# Breakouts3.net
KiCad netlist of a schematic drawn in EAGLE
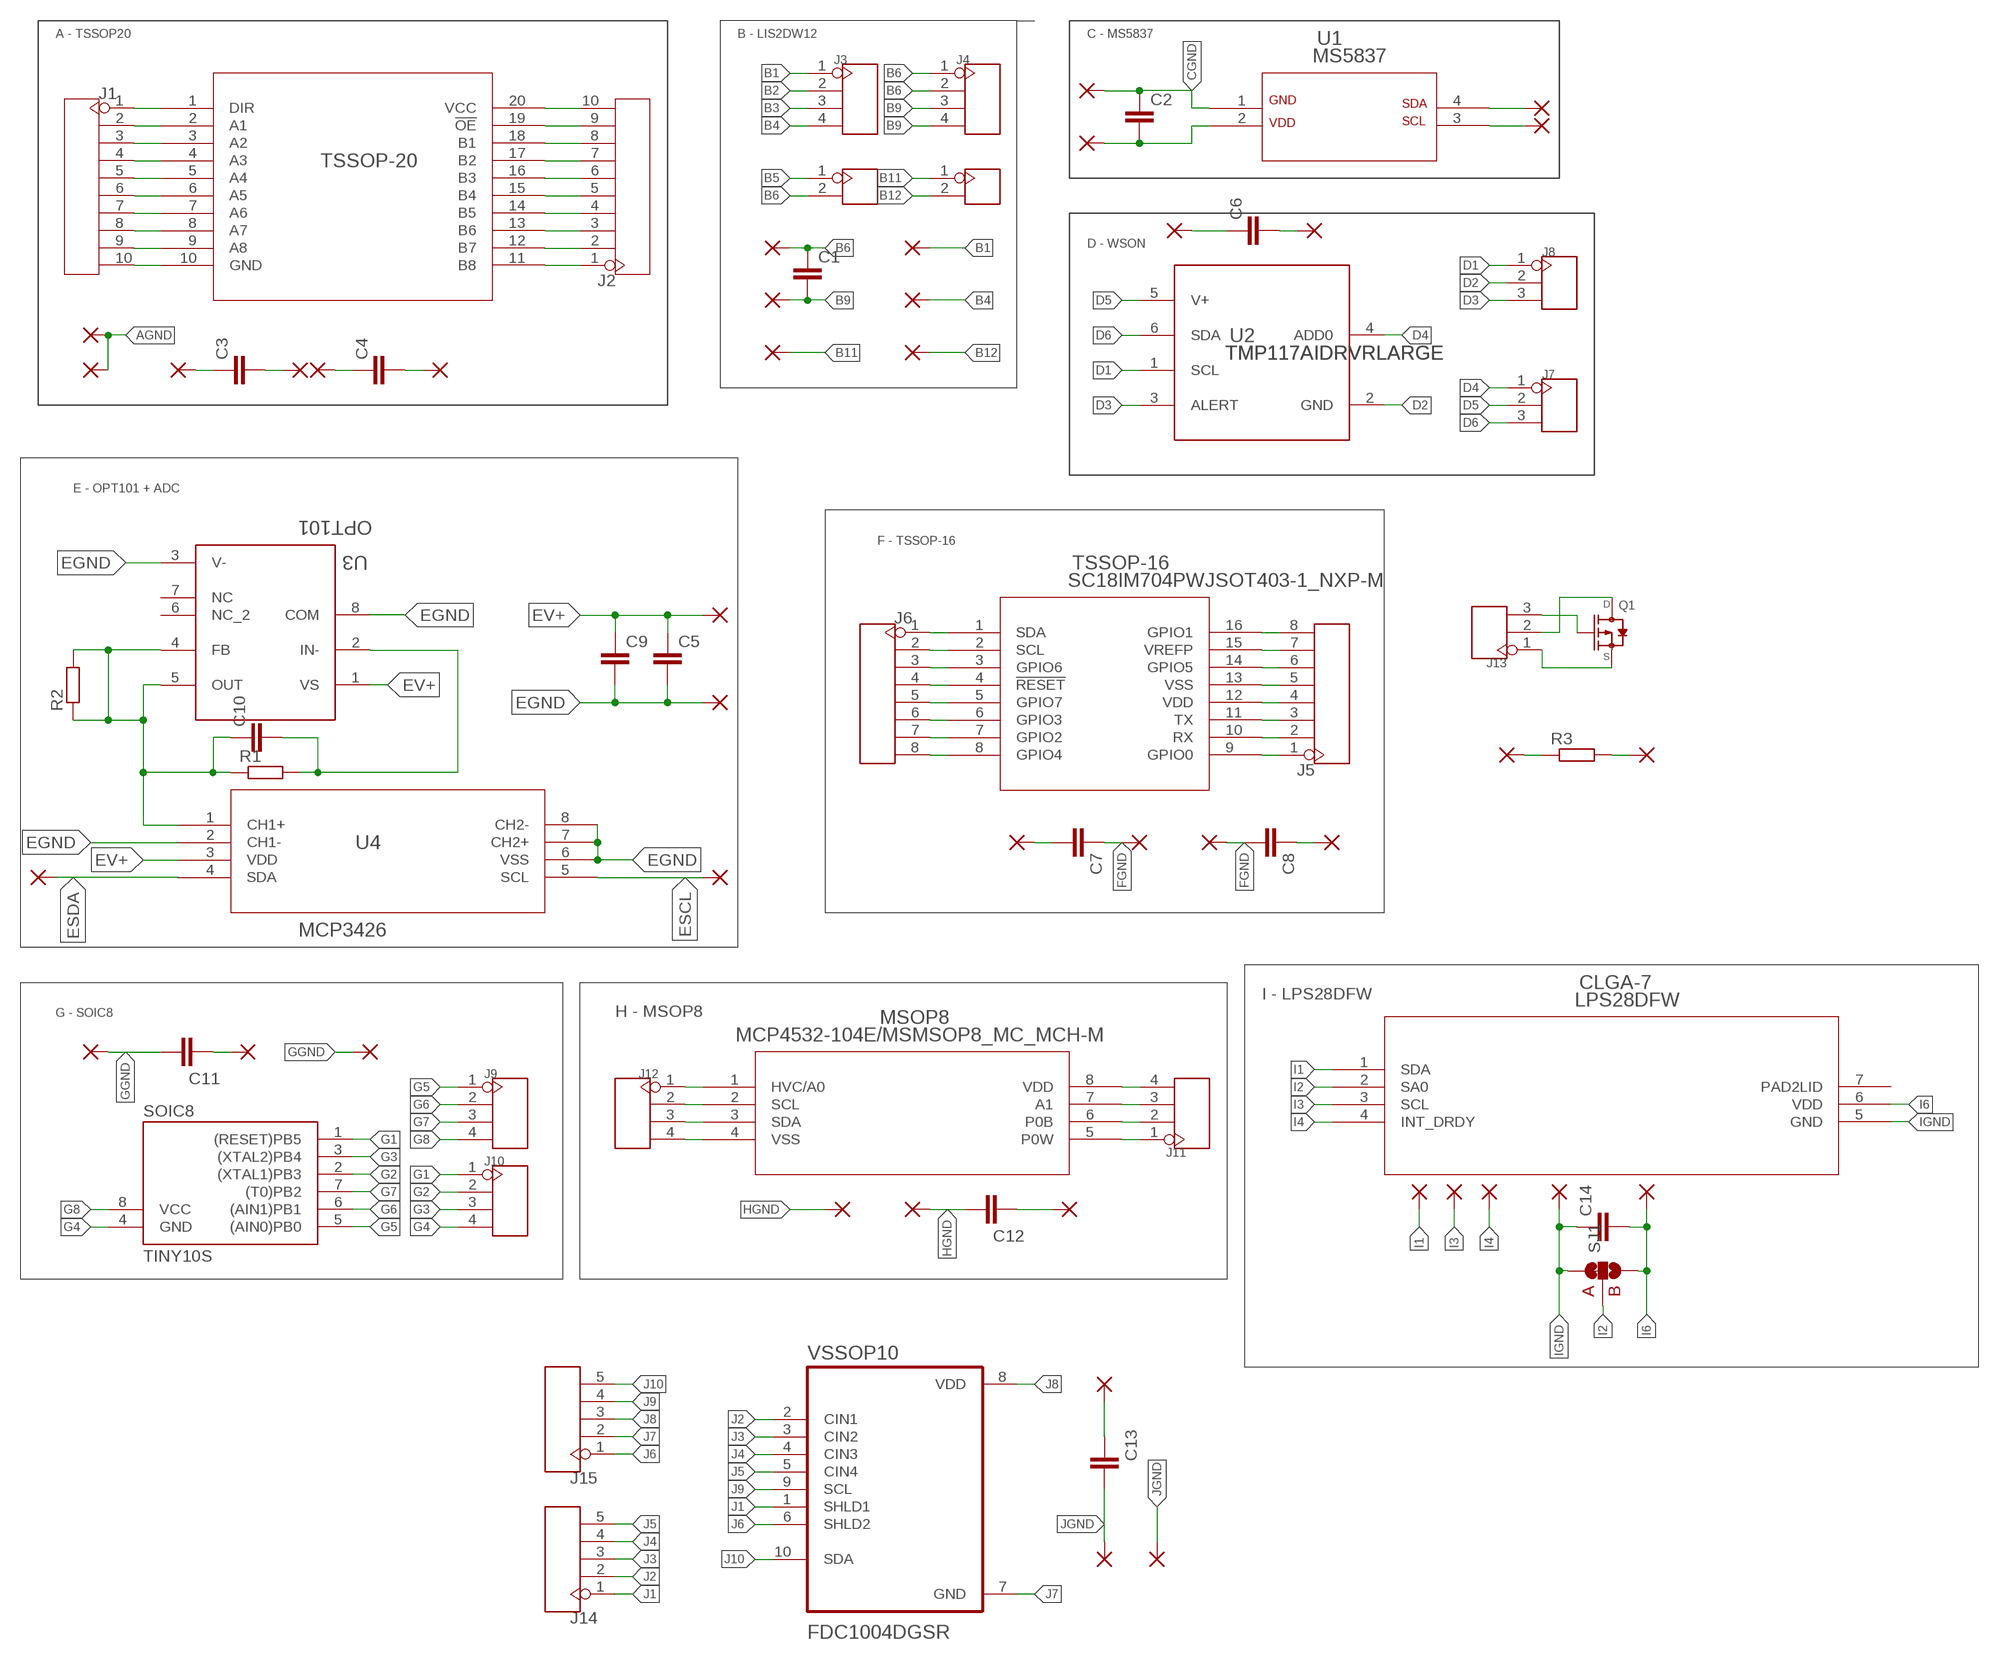
[diagram p0: schematic, sheet 1]

(export (version "E")
  (design (tool "Eeschema 10.0.6"))
  (components
    (comp (ref "C1")
      (value "C-EU1206")
      (footprint "eagle-import:1206")
      (libsource (lib "eagle-import") (part "C-EU1206"))
    )
    (comp (ref "C2")
      (value "C-EU1206")
      (footprint "eagle-import:1206")
      (libsource (lib "eagle-import") (part "C-EU1206"))
    )
    (comp (ref "C3")
      (value "C-EU1206")
      (footprint "eagle-import:1206")
      (libsource (lib "eagle-import") (part "C-EU1206"))
    )
    (comp (ref "C4")
      (value "C-EU1206")
      (footprint "eagle-import:1206")
      (libsource (lib "eagle-import") (part "C-EU1206"))
    )
    (comp (ref "C5")
      (value "C-EU1206")
      (footprint "eagle-import:1206")
      (libsource (lib "eagle-import") (part "C-EU1206"))
    )
    (comp (ref "C6")
      (value "C-EU1206")
      (footprint "eagle-import:1206")
      (libsource (lib "eagle-import") (part "C-EU1206"))
    )
    (comp (ref "C7")
      (value "C-EU1206")
      (footprint "eagle-import:1206")
      (libsource (lib "eagle-import") (part "C-EU1206"))
    )
    (comp (ref "C8")
      (value "C-EU1206")
      (footprint "eagle-import:1206")
      (libsource (lib "eagle-import") (part "C-EU1206"))
    )
    (comp (ref "C9")
      (value "C-EU1206")
      (footprint "eagle-import:1206")
      (libsource (lib "eagle-import") (part "C-EU1206"))
    )
    (comp (ref "C10")
      (value "C-EU1206")
      (footprint "eagle-import:1206")
      (libsource (lib "eagle-import") (part "C-EU1206"))
    )
    (comp (ref "C11")
      (value "C-EU1206")
      (footprint "eagle-import:1206")
      (libsource (lib "eagle-import") (part "C-EU1206"))
    )
    (comp (ref "C12")
      (value "C-EU1206")
      (footprint "eagle-import:1206")
      (libsource (lib "eagle-import") (part "C-EU1206"))
    )
    (comp (ref "C13")
      (value "C-EU1206")
      (footprint "eagle-import:1206")
      (libsource (lib "eagle-import") (part "C-EU1206"))
    )
    (comp (ref "C14")
      (value "C-EU1206")
      (footprint "eagle-import:1206")
      (libsource (lib "eagle-import") (part "C-EU1206"))
    )
    (comp (ref "CLGA-7")
      (value "LPS28DFW")
      (footprint "eagle-import:CCLGA7_LPS28DFW_LARGE")
      (libsource (lib "eagle-import") (part "LPS28DFWTRLARGE"))
    )
    (comp (ref "J1")
      (value "HEADER-10P-2.54")
      (footprint "eagle-import:10P-2.54")
      (libsource (lib "eagle-import") (part "HEADER-10P-2.54"))
    )
    (comp (ref "J2")
      (value "HEADER-10P-2.54")
      (footprint "eagle-import:10P-2.54")
      (libsource (lib "eagle-import") (part "HEADER-10P-2.54"))
    )
    (comp (ref "J3")
      (value "HEADER-4P-SMD-1.27")
      (footprint "eagle-import:4P-1.27-SMD")
      (libsource (lib "eagle-import") (part "SMD Breakouts_HEADER-4P-SMD-1.27"))
    )
    (comp (ref "J4")
      (value "HEADER-4P-SMD-1.27")
      (footprint "eagle-import:4P-1.27-SMD")
      (libsource (lib "eagle-import") (part "SMD Breakouts_HEADER-4P-SMD-1.27"))
    )
    (comp (ref "J5")
      (value "HEADER-8P-2.54")
      (footprint "eagle-import:8P-2.54")
      (libsource (lib "eagle-import") (part "HEADER-8P-2.54"))
    )
    (comp (ref "J6")
      (value "HEADER-8P-2.54")
      (footprint "eagle-import:8P-2.54")
      (libsource (lib "eagle-import") (part "HEADER-8P-2.54"))
    )
    (comp (ref "J7")
      (value "HEADER-3P-2.54")
      (footprint "eagle-import:3P-2.54")
      (libsource (lib "eagle-import") (part "HEADER-3P-2.54"))
    )
    (comp (ref "J8")
      (value "HEADER-3P-2.54")
      (footprint "eagle-import:3P-2.54")
      (libsource (lib "eagle-import") (part "HEADER-3P-2.54"))
    )
    (comp (ref "J9")
      (value "HEADER-4P-60/35MIL")
      (footprint "eagle-import:4P-65_35MIL")
      (libsource (lib "eagle-import") (part "HEADER-4P-60/35MIL"))
    )
    (comp (ref "J10")
      (value "HEADER-4P-60/35MIL")
      (footprint "eagle-import:4P-65_35MIL")
      (libsource (lib "eagle-import") (part "HEADER-4P-60/35MIL"))
    )
    (comp (ref "J11")
      (value "HEADER-4P-60/35MIL")
      (footprint "eagle-import:4P-65_35MIL")
      (libsource (lib "eagle-import") (part "HEADER-4P-60/35MIL"))
    )
    (comp (ref "J12")
      (value "HEADER-4P-60/35MIL")
      (footprint "eagle-import:4P-65_35MIL")
      (libsource (lib "eagle-import") (part "HEADER-4P-60/35MIL"))
    )
    (comp (ref "J13")
      (value "HEADER-3P-2.54")
      (footprint "eagle-import:3P-2.54")
      (libsource (lib "eagle-import") (part "HEADER-3P-2.54"))
    )
    (comp (ref "J14")
      (value "HEADER-5P-2.54")
      (footprint "eagle-import:5P-2.54")
      (libsource (lib "eagle-import") (part "HEADER-5P-2.54"))
    )
    (comp (ref "J15")
      (value "HEADER-5P-2.54")
      (footprint "eagle-import:5P-2.54")
      (libsource (lib "eagle-import") (part "HEADER-5P-2.54"))
    )
    (comp (ref "MSOP8")
      (value "MCP4532-104E/MSMSOP8_MC_MCH-M")
      (footprint "eagle-import:MSOP8_MC_MCH-M")
      (fields
        (field (name "MANUFACTURER_PART_NUMBER") "MCP4532-104E/MS")
        (field (name "COPYRIGHT") "Copyright (C) 2025 Ultra Librarian. All rights reserved.")
      )
      (libsource (lib "eagle-import") (part "MCP4532-104E/MSMSOP8_MC_MCH-M"))
    )
    (comp (ref "PAD1")
      (value "WIREPADSMD1,27-254")
      (footprint "eagle-import:SMD1,27-2,54")
      (libsource (lib "eagle-import") (part "WIREPADSMD1,27-254"))
    )
    (comp (ref "PAD2")
      (value "WIREPADSMD1,27-254")
      (footprint "eagle-import:SMD1,27-2,54")
      (libsource (lib "eagle-import") (part "WIREPADSMD1,27-254"))
    )
    (comp (ref "PAD3")
      (value "WIREPADSMD1,27-254")
      (footprint "eagle-import:SMD1,27-2,54")
      (libsource (lib "eagle-import") (part "WIREPADSMD1,27-254"))
    )
    (comp (ref "PAD4")
      (value "WIREPADSMD1,27-254")
      (footprint "eagle-import:SMD1,27-2,54")
      (libsource (lib "eagle-import") (part "WIREPADSMD1,27-254"))
    )
    (comp (ref "PAD5")
      (value "WIREPADSMD1,27-254")
      (footprint "eagle-import:SMD1,27-2,54")
      (libsource (lib "eagle-import") (part "WIREPADSMD1,27-254"))
    )
    (comp (ref "PAD6")
      (value "WIREPADSMD1,27-254")
      (footprint "eagle-import:SMD1,27-2,54")
      (libsource (lib "eagle-import") (part "WIREPADSMD1,27-254"))
    )
    (comp (ref "PAD7")
      (value "WIREPADSMD1,27-254")
      (footprint "eagle-import:SMD1,27-2,54")
      (libsource (lib "eagle-import") (part "WIREPADSMD1,27-254"))
    )
    (comp (ref "PAD8")
      (value "WIREPADSMD1,27-254")
      (footprint "eagle-import:SMD1,27-2,54")
      (libsource (lib "eagle-import") (part "WIREPADSMD1,27-254"))
    )
    (comp (ref "PAD9")
      (value "WIREPADSMD1,27-254")
      (footprint "eagle-import:SMD1,27-2,54")
      (libsource (lib "eagle-import") (part "WIREPADSMD1,27-254"))
    )
    (comp (ref "PAD10")
      (value "WIREPADSMD1,27-254")
      (footprint "eagle-import:SMD1,27-2,54")
      (libsource (lib "eagle-import") (part "WIREPADSMD1,27-254"))
    )
    (comp (ref "PAD11")
      (value "WIREPADSMD1,27-254")
      (footprint "eagle-import:SMD1,27-2,54")
      (libsource (lib "eagle-import") (part "WIREPADSMD1,27-254"))
    )
    (comp (ref "PAD12")
      (value "WIREPADSMD1,27-254")
      (footprint "eagle-import:SMD1,27-2,54")
      (libsource (lib "eagle-import") (part "WIREPADSMD1,27-254"))
    )
    (comp (ref "PAD13")
      (value "WIREPADSMD1,27-254")
      (footprint "eagle-import:SMD1,27-2,54")
      (libsource (lib "eagle-import") (part "WIREPADSMD1,27-254"))
    )
    (comp (ref "PAD14")
      (value "WIREPADSMD1,27-254")
      (footprint "eagle-import:SMD1,27-2,54")
      (libsource (lib "eagle-import") (part "WIREPADSMD1,27-254"))
    )
    (comp (ref "PAD15")
      (value "WIREPADSMD1,27-254")
      (footprint "eagle-import:SMD1,27-2,54")
      (libsource (lib "eagle-import") (part "WIREPADSMD1,27-254"))
    )
    (comp (ref "PAD16")
      (value "WIREPADSMD1,27-254")
      (footprint "eagle-import:SMD1,27-2,54")
      (libsource (lib "eagle-import") (part "WIREPADSMD1,27-254"))
    )
    (comp (ref "PAD17")
      (value "WIREPADSMD1,27-254")
      (footprint "eagle-import:SMD1,27-2,54")
      (libsource (lib "eagle-import") (part "WIREPADSMD1,27-254"))
    )
    (comp (ref "PAD18")
      (value "WIREPADSMD1,27-254")
      (footprint "eagle-import:SMD1,27-2,54")
      (libsource (lib "eagle-import") (part "WIREPADSMD1,27-254"))
    )
    (comp (ref "PAD19")
      (value "WIREPADSMD1,27-254")
      (footprint "eagle-import:SMD1,27-2,54")
      (libsource (lib "eagle-import") (part "WIREPADSMD1,27-254"))
    )
    (comp (ref "PAD20")
      (value "WIREPADSMD1,27-254")
      (footprint "eagle-import:SMD1,27-2,54")
      (libsource (lib "eagle-import") (part "WIREPADSMD1,27-254"))
    )
    (comp (ref "PAD21")
      (value "WIREPADSMD1,27-254")
      (footprint "eagle-import:SMD1,27-2,54")
      (libsource (lib "eagle-import") (part "WIREPADSMD1,27-254"))
    )
    (comp (ref "PAD22")
      (value "WIREPADSMD1,27-254")
      (footprint "eagle-import:SMD1,27-2,54")
      (libsource (lib "eagle-import") (part "WIREPADSMD1,27-254"))
    )
    (comp (ref "PAD23")
      (value "WIREPADSMD1,27-254")
      (footprint "eagle-import:SMD1,27-2,54")
      (libsource (lib "eagle-import") (part "WIREPADSMD1,27-254"))
    )
    (comp (ref "PAD24")
      (value "WIREPADSMD1,27-254")
      (footprint "eagle-import:SMD1,27-2,54")
      (libsource (lib "eagle-import") (part "WIREPADSMD1,27-254"))
    )
    (comp (ref "PAD25")
      (value "WIREPADSMD1,27-254")
      (footprint "eagle-import:SMD1,27-2,54")
      (libsource (lib "eagle-import") (part "WIREPADSMD1,27-254"))
    )
    (comp (ref "PAD26")
      (value "WIREPADSMD1,27-254")
      (footprint "eagle-import:SMD1,27-2,54")
      (libsource (lib "eagle-import") (part "WIREPADSMD1,27-254"))
    )
    (comp (ref "PAD27")
      (value "WIREPADSMD1,27-254")
      (footprint "eagle-import:SMD1,27-2,54")
      (libsource (lib "eagle-import") (part "WIREPADSMD1,27-254"))
    )
    (comp (ref "PAD28")
      (value "WIREPADSMD1,27-254")
      (footprint "eagle-import:SMD1,27-2,54")
      (libsource (lib "eagle-import") (part "WIREPADSMD1,27-254"))
    )
    (comp (ref "PAD29")
      (value "WIREPADSMD1,27-254")
      (footprint "eagle-import:SMD1,27-2,54")
      (libsource (lib "eagle-import") (part "WIREPADSMD1,27-254"))
    )
    (comp (ref "PAD30")
      (value "WIREPADSMD1,27-254")
      (footprint "eagle-import:SMD1,27-2,54")
      (libsource (lib "eagle-import") (part "WIREPADSMD1,27-254"))
    )
    (comp (ref "PAD31")
      (value "WIREPADSMD1,27-254")
      (footprint "eagle-import:SMD1,27-2,54")
      (libsource (lib "eagle-import") (part "WIREPADSMD1,27-254"))
    )
    (comp (ref "PAD32")
      (value "WIREPADSMD1,27-254")
      (footprint "eagle-import:SMD1,27-2,54")
      (libsource (lib "eagle-import") (part "WIREPADSMD1,27-254"))
    )
    (comp (ref "PAD33")
      (value "WIREPADSMD1,27-254")
      (footprint "eagle-import:SMD1,27-2,54")
      (libsource (lib "eagle-import") (part "WIREPADSMD1,27-254"))
    )
    (comp (ref "PAD34")
      (value "WIREPADSMD1,27-254")
      (footprint "eagle-import:SMD1,27-2,54")
      (libsource (lib "eagle-import") (part "WIREPADSMD1,27-254"))
    )
    (comp (ref "PAD35")
      (value "WIREPADSMD1,27-254")
      (footprint "eagle-import:SMD1,27-2,54")
      (libsource (lib "eagle-import") (part "WIREPADSMD1,27-254"))
    )
    (comp (ref "PAD36")
      (value "WIREPADSMD1,27-254")
      (footprint "eagle-import:SMD1,27-2,54")
      (libsource (lib "eagle-import") (part "WIREPADSMD1,27-254"))
    )
    (comp (ref "PAD37")
      (value "WIREPADSMD1,27-254")
      (footprint "eagle-import:SMD1,27-2,54")
      (libsource (lib "eagle-import") (part "WIREPADSMD1,27-254"))
    )
    (comp (ref "PAD38")
      (value "WIREPADSMD1,27-254")
      (footprint "eagle-import:SMD1,27-2,54")
      (libsource (lib "eagle-import") (part "WIREPADSMD1,27-254"))
    )
    (comp (ref "PAD39")
      (value "WIREPADSMD1,27-254")
      (footprint "eagle-import:SMD1,27-2,54")
      (libsource (lib "eagle-import") (part "WIREPADSMD1,27-254"))
    )
    (comp (ref "PAD40")
      (value "WIREPADSMD1,27-254")
      (footprint "eagle-import:SMD1,27-2,54")
      (libsource (lib "eagle-import") (part "WIREPADSMD1,27-254"))
    )
    (comp (ref "PAD41")
      (value "WIREPADSMD1,27-254")
      (footprint "eagle-import:SMD1,27-2,54")
      (libsource (lib "eagle-import") (part "WIREPADSMD1,27-254"))
    )
    (comp (ref "PAD42")
      (value "WIREPADSMD1,27-254")
      (footprint "eagle-import:SMD1,27-2,54")
      (libsource (lib "eagle-import") (part "WIREPADSMD1,27-254"))
    )
    (comp (ref "Q1")
      (value "FDN338P_PMOSSOT23_LONG")
      (footprint "eagle-import:SOT23_LONG")
      (libsource (lib "eagle-import") (part "FDN338P_PMOSSOT23_LONG"))
    )
    (comp (ref "R1")
      (value "R-EU_")
      (footprint "eagle-import:1206")
      (libsource (lib "eagle-import") (part "R-EU_"))
    )
    (comp (ref "R2")
      (value "R-EU_")
      (footprint "eagle-import:1206")
      (libsource (lib "eagle-import") (part "R-EU_"))
    )
    (comp (ref "R3")
      (value "R-EU_")
      (footprint "eagle-import:1206")
      (libsource (lib "eagle-import") (part "R-EU_"))
    )
    (comp (ref "SJ1")
      (value "SOLDERJUMPER_2WAYT")
      (footprint "eagle-import:SJ_2")
      (libsource (lib "eagle-import") (part "SOLDERJUMPER_2WAYT"))
    )
    (comp (ref "SOIC8")
      (value "TINY10S")
      (footprint "eagle-import:SOIC8")
      (libsource (lib "eagle-import") (part "TINY10S"))
    )
    (comp (ref "TSSOP-16")
      (value "SC18IM704PWJSOT403-1_NXP-M")
      (footprint "eagle-import:SOT403-1_NXP-M")
      (fields
        (field (name "MANUFACTURER_PART_NUMBER") "SC18IM704PWJ")
        (field (name "COPYRIGHT") "Copyright (C) 2025 Ultra Librarian. All rights reserved.")
      )
      (libsource (lib "eagle-import") (part "SC18IM704PWJSOT403-1_NXP-M"))
    )
    (comp (ref "TSSOP-20")
      (value "SN74ACT245PWRPW20-M")
      (footprint "eagle-import:PW20-M")
      (fields
        (field (name "MANUFACTURER_PART_NUMBER") "SN74ACT245PWR")
        (field (name "COPYRIGHT") "Copyright (C) 2025 Ultra Librarian. All rights reserved.")
      )
      (libsource (lib "eagle-import") (part "SN74ACT245PWRPW20-M"))
    )
    (comp (ref "U$1")
      (value "HEADER-2P")
      (footprint "eagle-import:2P-1.27-SMD")
      (libsource (lib "eagle-import") (part "HEADER-2P"))
    )
    (comp (ref "U$2")
      (value "HEADER-2P")
      (footprint "eagle-import:2P-1.27-SMD")
      (libsource (lib "eagle-import") (part "HEADER-2P"))
    )
    (comp (ref "U1")
      (value "MS5837")
      (footprint "eagle-import:MS5837-02BA01_LARGE")
      (libsource (lib "eagle-import") (part "MS583702BA01-50LARGE"))
    )
    (comp (ref "U2")
      (value "TMP117AIDRVRLARGE")
      (footprint "eagle-import:DRV0006B-LARGE")
      (libsource (lib "eagle-import") (part "TMP117AIDRVRLARGE"))
    )
    (comp (ref "U3")
      (value "OPT101")
      (footprint "eagle-import:DTL0008A_LARGE")
      (libsource (lib "eagle-import") (part "OPT101P-JLARGE"))
    )
    (comp (ref "U4")
      (value "MCP3426")
      (footprint "eagle-import:SOIC8-N_MC_MCH")
      (fields
        (field (name "MANUFACTURER_PART_NUMBER") "MCP3426A0T-E/SN")
        (field (name "COPYRIGHT") "Copyright (C) 2025 Ultra Librarian. All rights reserved.")
      )
      (libsource (lib "eagle-import") (part "MCP3426A0T-E/SN"))
    )
    (comp (ref "VSSOP10")
      (value "FDC1004DGSR")
      (footprint "eagle-import:SOP50P490X110-10N")
      (libsource (lib "eagle-import") (part "FDC1004DGSR"))
    )
  )
  (nets
    (net (code "1") (name "AGND") (class "Default")
      (node (ref "PAD15") (pin "1") (pinfunction "P_1") (pintype "passive"))
      (node (ref "PAD16") (pin "1") (pinfunction "P_1") (pintype "passive"))
    )
    (net (code "2") (name "B1") (class "Default")
      (node (ref "J3") (pin "1") (pinfunction "P$1_1") (pintype "bidirectional"))
      (node (ref "PAD3") (pin "1") (pinfunction "P_1") (pintype "passive"))
    )
    (net (code "3") (name "B2") (class "Default")
      (node (ref "J3") (pin "2") (pinfunction "P$2_2") (pintype "bidirectional"))
    )
    (net (code "4") (name "B3") (class "Default")
      (node (ref "J3") (pin "3") (pinfunction "P$3_3") (pintype "bidirectional"))
    )
    (net (code "5") (name "B4") (class "Default")
      (node (ref "J3") (pin "4") (pinfunction "P$4_4") (pintype "bidirectional"))
      (node (ref "PAD6") (pin "1") (pinfunction "P_1") (pintype "passive"))
    )
    (net (code "6") (name "B5") (class "Default")
      (node (ref "U$1") (pin "1") (pinfunction "P$1_1") (pintype "bidirectional"))
    )
    (net (code "7") (name "B6") (class "Default")
      (node (ref "C1") (pin "1") (pinfunction "1_1") (pintype "passive"))
      (node (ref "J4") (pin "1") (pinfunction "P$1_1") (pintype "bidirectional"))
      (node (ref "J4") (pin "2") (pinfunction "P$2_2") (pintype "bidirectional"))
      (node (ref "PAD1") (pin "1") (pinfunction "P_1") (pintype "passive"))
      (node (ref "U$1") (pin "2") (pinfunction "P$2_2") (pintype "bidirectional"))
    )
    (net (code "8") (name "B9") (class "Default")
      (node (ref "C1") (pin "2") (pinfunction "2_2") (pintype "passive"))
      (node (ref "J4") (pin "3") (pinfunction "P$3_3") (pintype "bidirectional"))
      (node (ref "J4") (pin "4") (pinfunction "P$4_4") (pintype "bidirectional"))
      (node (ref "PAD2") (pin "1") (pinfunction "P_1") (pintype "passive"))
    )
    (net (code "9") (name "B11") (class "Default")
      (node (ref "PAD4") (pin "1") (pinfunction "P_1") (pintype "passive"))
      (node (ref "U$2") (pin "1") (pinfunction "P$1_1") (pintype "bidirectional"))
    )
    (net (code "10") (name "B12") (class "Default")
      (node (ref "PAD5") (pin "1") (pinfunction "P_1") (pintype "passive"))
      (node (ref "U$2") (pin "2") (pinfunction "P$2_2") (pintype "bidirectional"))
    )
    (net (code "11") (name "CGND") (class "Default")
      (node (ref "C2") (pin "1") (pinfunction "1_1") (pintype "passive"))
      (node (ref "PAD7") (pin "1") (pinfunction "P_1") (pintype "passive"))
      (node (ref "U1") (pin "1") (pinfunction "GND_1") (pintype "passive"))
    )
    (net (code "12") (name "D1") (class "Default")
      (node (ref "J8") (pin "1") (pinfunction "P$1_1") (pintype "bidirectional"))
      (node (ref "U2") (pin "1") (pinfunction "SCL_1") (pintype "open_collector"))
    )
    (net (code "13") (name "D2") (class "Default")
      (node (ref "J8") (pin "2") (pinfunction "P$2_2") (pintype "bidirectional"))
      (node (ref "U2") (pin "2") (pinfunction "GND_2") (pintype "power_in"))
    )
    (net (code "14") (name "D3") (class "Default")
      (node (ref "J8") (pin "3") (pinfunction "P$3_3") (pintype "bidirectional"))
      (node (ref "U2") (pin "3") (pinfunction "ALERT_3") (pintype "open_collector"))
    )
    (net (code "15") (name "D4") (class "Default")
      (node (ref "J7") (pin "1") (pinfunction "P$1_1") (pintype "bidirectional"))
      (node (ref "U2") (pin "4") (pinfunction "ADD0_4") (pintype "input"))
    )
    (net (code "16") (name "D5") (class "Default")
      (node (ref "J7") (pin "2") (pinfunction "P$2_2") (pintype "bidirectional"))
      (node (ref "U2") (pin "5") (pinfunction "V+_5") (pintype "power_in"))
    )
    (net (code "17") (name "D6") (class "Default")
      (node (ref "J7") (pin "3") (pinfunction "P$3_3") (pintype "bidirectional"))
      (node (ref "U2") (pin "6") (pinfunction "SDA_6") (pintype "bidirectional"))
    )
    (net (code "18") (name "EGND") (class "Default")
      (node (ref "C5") (pin "2") (pinfunction "2_2") (pintype "passive"))
      (node (ref "C9") (pin "2") (pinfunction "2_2") (pintype "passive"))
      (node (ref "PAD24") (pin "1") (pinfunction "P_1") (pintype "passive"))
      (node (ref "U3") (pin "3") (pinfunction "V-_3") (pintype "power_in"))
      (node (ref "U3") (pin "8") (pinfunction "COM_8") (pintype "passive"))
      (node (ref "U4") (pin "2") (pinfunction "CH1-_2") (pintype "input"))
      (node (ref "U4") (pin "6") (pinfunction "VSS_6") (pintype "power_in"))
      (node (ref "U4") (pin "7") (pinfunction "CH2+_7") (pintype "input"))
      (node (ref "U4") (pin "8") (pinfunction "CH2-_8") (pintype "input"))
    )
    (net (code "19") (name "ESCL") (class "Default")
      (node (ref "PAD25") (pin "1") (pinfunction "P_1") (pintype "passive"))
      (node (ref "U4") (pin "5") (pinfunction "SCL_5") (pintype "input"))
    )
    (net (code "20") (name "ESDA") (class "Default")
      (node (ref "PAD26") (pin "1") (pinfunction "P_1") (pintype "passive"))
      (node (ref "U4") (pin "4") (pinfunction "SDA_4") (pintype "bidirectional"))
    )
    (net (code "21") (name "EV+") (class "Default")
      (node (ref "C5") (pin "1") (pinfunction "1_1") (pintype "passive"))
      (node (ref "C9") (pin "1") (pinfunction "1_1") (pintype "passive"))
      (node (ref "PAD23") (pin "1") (pinfunction "P_1") (pintype "passive"))
      (node (ref "U3") (pin "1") (pinfunction "VS_1") (pintype "power_in"))
      (node (ref "U4") (pin "3") (pinfunction "VDD_3") (pintype "power_in"))
    )
    (net (code "22") (name "FGND") (class "Default")
      (node (ref "C7") (pin "1") (pinfunction "1_1") (pintype "passive"))
      (node (ref "C8") (pin "2") (pinfunction "2_2") (pintype "passive"))
      (node (ref "PAD20") (pin "1") (pinfunction "P_1") (pintype "passive"))
      (node (ref "PAD21") (pin "1") (pinfunction "P_1") (pintype "passive"))
    )
    (net (code "23") (name "G1") (class "Default")
      (node (ref "J10") (pin "1") (pinfunction "P$1_1") (pintype "bidirectional"))
      (node (ref "SOIC8") (pin "1") (pinfunction "(RESET)PB5_1") (pintype "bidirectional"))
    )
    (net (code "24") (name "G2") (class "Default")
      (node (ref "J10") (pin "2") (pinfunction "P$2_2") (pintype "bidirectional"))
      (node (ref "SOIC8") (pin "2") (pinfunction "(XTAL1)PB3_2") (pintype "bidirectional"))
    )
    (net (code "25") (name "G3") (class "Default")
      (node (ref "J10") (pin "3") (pinfunction "P$3_3") (pintype "bidirectional"))
      (node (ref "SOIC8") (pin "3") (pinfunction "(XTAL2)PB4_3") (pintype "bidirectional"))
    )
    (net (code "26") (name "G4") (class "Default")
      (node (ref "J10") (pin "4") (pinfunction "P$4_4") (pintype "bidirectional"))
      (node (ref "SOIC8") (pin "4") (pinfunction "GND_4") (pintype "power_in"))
    )
    (net (code "27") (name "G5") (class "Default")
      (node (ref "J9") (pin "1") (pinfunction "P$1_1") (pintype "bidirectional"))
      (node (ref "SOIC8") (pin "5") (pinfunction "(AIN0)PB0_5") (pintype "bidirectional"))
    )
    (net (code "28") (name "G6") (class "Default")
      (node (ref "J9") (pin "2") (pinfunction "P$2_2") (pintype "bidirectional"))
      (node (ref "SOIC8") (pin "6") (pinfunction "(AIN1)PB1_6") (pintype "bidirectional"))
    )
    (net (code "29") (name "G7") (class "Default")
      (node (ref "J9") (pin "3") (pinfunction "P$3_3") (pintype "bidirectional"))
      (node (ref "SOIC8") (pin "7") (pinfunction "(T0)PB2_7") (pintype "bidirectional"))
    )
    (net (code "30") (name "G8") (class "Default")
      (node (ref "J9") (pin "4") (pinfunction "P$4_4") (pintype "bidirectional"))
      (node (ref "SOIC8") (pin "8") (pinfunction "VCC_8") (pintype "power_in"))
    )
    (net (code "31") (name "GGND") (class "Default")
      (node (ref "C11") (pin "1") (pinfunction "1_1") (pintype "passive"))
      (node (ref "PAD27") (pin "1") (pinfunction "P_1") (pintype "passive"))
      (node (ref "PAD29") (pin "1") (pinfunction "P_1") (pintype "passive"))
    )
    (net (code "32") (name "HGND") (class "Default")
      (node (ref "C12") (pin "1") (pinfunction "1_1") (pintype "passive"))
      (node (ref "PAD31") (pin "1") (pinfunction "P_1") (pintype "passive"))
      (node (ref "PAD32") (pin "1") (pinfunction "P_1") (pintype "passive"))
    )
    (net (code "33") (name "I1") (class "Default")
      (node (ref "CLGA-7") (pin "1") (pinfunction "SDA_1") (pintype "bidirectional"))
      (node (ref "PAD34") (pin "1") (pinfunction "P_1") (pintype "passive"))
    )
    (net (code "34") (name "I2") (class "Default")
      (node (ref "CLGA-7") (pin "2") (pinfunction "SA0_2") (pintype "bidirectional"))
      (node (ref "SJ1") (pin "2") (pinfunction "2_2") (pintype "passive"))
    )
    (net (code "35") (name "I3") (class "Default")
      (node (ref "CLGA-7") (pin "3") (pinfunction "SCL_3") (pintype "bidirectional"))
      (node (ref "PAD35") (pin "1") (pinfunction "P_1") (pintype "passive"))
    )
    (net (code "36") (name "I4") (class "Default")
      (node (ref "CLGA-7") (pin "4") (pinfunction "INT_DRDY_4") (pintype "input"))
      (node (ref "PAD36") (pin "1") (pinfunction "P_1") (pintype "passive"))
    )
    (net (code "37") (name "I6") (class "Default")
      (node (ref "C14") (pin "2") (pinfunction "2_2") (pintype "passive"))
      (node (ref "CLGA-7") (pin "6") (pinfunction "VDD_6") (pintype "power_in"))
      (node (ref "PAD38") (pin "1") (pinfunction "P_1") (pintype "passive"))
      (node (ref "SJ1") (pin "3") (pinfunction "3_3") (pintype "passive"))
    )
    (net (code "38") (name "IGND") (class "Default")
      (node (ref "C14") (pin "1") (pinfunction "1_1") (pintype "passive"))
      (node (ref "CLGA-7") (pin "5") (pinfunction "GND_5") (pintype "passive"))
      (node (ref "PAD37") (pin "1") (pinfunction "P_1") (pintype "passive"))
      (node (ref "SJ1") (pin "1") (pinfunction "1_1") (pintype "passive"))
    )
    (net (code "39") (name "J1") (class "Default")
      (node (ref "J14") (pin "1") (pinfunction "1_1") (pintype "bidirectional"))
      (node (ref "VSSOP10") (pin "1") (pinfunction "SHLD1_1") (pintype "input"))
    )
    (net (code "40") (name "J2") (class "Default")
      (node (ref "J14") (pin "2") (pinfunction "2_2") (pintype "bidirectional"))
      (node (ref "VSSOP10") (pin "2") (pinfunction "CIN1_2") (pintype "input"))
    )
    (net (code "41") (name "J3") (class "Default")
      (node (ref "J14") (pin "3") (pinfunction "3_3") (pintype "bidirectional"))
      (node (ref "VSSOP10") (pin "3") (pinfunction "CIN2_3") (pintype "input"))
    )
    (net (code "42") (name "J4") (class "Default")
      (node (ref "J14") (pin "4") (pinfunction "4_4") (pintype "bidirectional"))
      (node (ref "VSSOP10") (pin "4") (pinfunction "CIN3_4") (pintype "input"))
    )
    (net (code "43") (name "J5") (class "Default")
      (node (ref "J14") (pin "5") (pinfunction "5_5") (pintype "bidirectional"))
      (node (ref "VSSOP10") (pin "5") (pinfunction "CIN4_5") (pintype "input"))
    )
    (net (code "44") (name "J6") (class "Default")
      (node (ref "J15") (pin "1") (pinfunction "1_1") (pintype "bidirectional"))
      (node (ref "VSSOP10") (pin "6") (pinfunction "SHLD2_6") (pintype "input"))
    )
    (net (code "45") (name "J7") (class "Default")
      (node (ref "J15") (pin "2") (pinfunction "2_2") (pintype "bidirectional"))
      (node (ref "VSSOP10") (pin "7") (pinfunction "GND_7") (pintype "power_in"))
    )
    (net (code "46") (name "J8") (class "Default")
      (node (ref "J15") (pin "3") (pinfunction "3_3") (pintype "bidirectional"))
      (node (ref "VSSOP10") (pin "8") (pinfunction "VDD_8") (pintype "power_in"))
    )
    (net (code "47") (name "J9") (class "Default")
      (node (ref "J15") (pin "4") (pinfunction "4_4") (pintype "bidirectional"))
      (node (ref "VSSOP10") (pin "9") (pinfunction "SCL_9") (pintype "input"))
    )
    (net (code "48") (name "J10") (class "Default")
      (node (ref "J15") (pin "5") (pinfunction "5_5") (pintype "bidirectional"))
      (node (ref "VSSOP10") (pin "10") (pinfunction "SDA_10") (pintype "bidirectional"))
    )
    (net (code "49") (name "JGND") (class "Default")
      (node (ref "C13") (pin "1") (pinfunction "1_1") (pintype "passive"))
      (node (ref "PAD41") (pin "1") (pinfunction "P_1") (pintype "passive"))
      (node (ref "PAD42") (pin "1") (pinfunction "P_1") (pintype "passive"))
    )
    (net (code "50") (name "Net-(J11-P$1)") (class "Default")
      (node (ref "J11") (pin "1") (pinfunction "P$1_1") (pintype "bidirectional"))
      (node (ref "MSOP8") (pin "5") (pinfunction "P0W_5") (pintype "passive"))
    )
    (net (code "51") (name "Net-(J11-P$2)") (class "Default")
      (node (ref "J11") (pin "2") (pinfunction "P$2_2") (pintype "bidirectional"))
      (node (ref "MSOP8") (pin "6") (pinfunction "P0B_6") (pintype "passive"))
    )
    (net (code "52") (name "Net-(J11-P$3)") (class "Default")
      (node (ref "J11") (pin "3") (pinfunction "P$3_3") (pintype "bidirectional"))
      (node (ref "MSOP8") (pin "7") (pinfunction "A1_7") (pintype "input"))
    )
    (net (code "53") (name "Net-(J11-P$4)") (class "Default")
      (node (ref "J11") (pin "4") (pinfunction "P$4_4") (pintype "bidirectional"))
      (node (ref "MSOP8") (pin "8") (pinfunction "VDD_8") (pintype "power_in"))
    )
    (net (code "54") (name "Net-(J12-P$1)") (class "Default")
      (node (ref "J12") (pin "1") (pinfunction "P$1_1") (pintype "bidirectional"))
      (node (ref "MSOP8") (pin "1") (pinfunction "HVC/A0_1") (pintype "input"))
    )
    (net (code "55") (name "Net-(J12-P$2)") (class "Default")
      (node (ref "J12") (pin "2") (pinfunction "P$2_2") (pintype "bidirectional"))
      (node (ref "MSOP8") (pin "2") (pinfunction "SCL_2") (pintype "input"))
    )
    (net (code "56") (name "Net-(J12-P$3)") (class "Default")
      (node (ref "J12") (pin "3") (pinfunction "P$3_3") (pintype "bidirectional"))
      (node (ref "MSOP8") (pin "3") (pinfunction "SDA_3") (pintype "bidirectional"))
    )
    (net (code "57") (name "Net-(J12-P$4)") (class "Default")
      (node (ref "J12") (pin "4") (pinfunction "P$4_4") (pintype "bidirectional"))
      (node (ref "MSOP8") (pin "4") (pinfunction "VSS_4") (pintype "power_in"))
    )
    (net (code "58") (name "Net-(J13-P$1)") (class "Default")
      (node (ref "J13") (pin "1") (pinfunction "P$1_1") (pintype "bidirectional"))
      (node (ref "Q1") (pin "2") (pinfunction "S_2") (pintype "passive"))
    )
    (net (code "59") (name "Net-(J13-P$2)") (class "Default")
      (node (ref "J13") (pin "2") (pinfunction "P$2_2") (pintype "bidirectional"))
      (node (ref "Q1") (pin "3") (pinfunction "D_3") (pintype "passive"))
    )
    (net (code "60") (name "Net-(J13-P$3)") (class "Default")
      (node (ref "J13") (pin "3") (pinfunction "P$3_3") (pintype "bidirectional"))
      (node (ref "Q1") (pin "1") (pinfunction "G_1") (pintype "passive"))
    )
    (net (code "61") (name "Net-(PAD8-P)") (class "Default")
      (node (ref "C2") (pin "2") (pinfunction "2_2") (pintype "passive"))
      (node (ref "PAD8") (pin "1") (pinfunction "P_1") (pintype "passive"))
      (node (ref "U1") (pin "2") (pinfunction "VDD_2") (pintype "power_in"))
    )
    (net (code "62") (name "Net-(PAD9-P)") (class "Default")
      (node (ref "PAD9") (pin "1") (pinfunction "P_1") (pintype "passive"))
      (node (ref "U1") (pin "4") (pinfunction "SDA_4") (pintype "passive"))
    )
    (net (code "63") (name "Net-(PAD10-P)") (class "Default")
      (node (ref "PAD10") (pin "1") (pinfunction "P_1") (pintype "passive"))
      (node (ref "U1") (pin "3") (pinfunction "SCL_3") (pintype "input"))
    )
    (net (code "64") (name "Net-(PAD11-P)") (class "Default")
      (node (ref "C3") (pin "1") (pinfunction "1_1") (pintype "passive"))
      (node (ref "PAD11") (pin "1") (pinfunction "P_1") (pintype "passive"))
    )
    (net (code "65") (name "Net-(PAD12-P)") (class "Default")
      (node (ref "C4") (pin "1") (pinfunction "1_1") (pintype "passive"))
      (node (ref "PAD12") (pin "1") (pinfunction "P_1") (pintype "passive"))
    )
    (net (code "66") (name "Net-(PAD13-P)") (class "Default")
      (node (ref "C3") (pin "2") (pinfunction "2_2") (pintype "passive"))
      (node (ref "PAD13") (pin "1") (pinfunction "P_1") (pintype "passive"))
    )
    (net (code "67") (name "Net-(PAD14-P)") (class "Default")
      (node (ref "C4") (pin "2") (pinfunction "2_2") (pintype "passive"))
      (node (ref "PAD14") (pin "1") (pinfunction "P_1") (pintype "passive"))
    )
    (net (code "68") (name "Net-(PAD17-P)") (class "Default")
      (node (ref "C6") (pin "1") (pinfunction "1_1") (pintype "passive"))
      (node (ref "PAD17") (pin "1") (pinfunction "P_1") (pintype "passive"))
    )
    (net (code "69") (name "Net-(PAD18-P)") (class "Default")
      (node (ref "C6") (pin "2") (pinfunction "2_2") (pintype "passive"))
      (node (ref "PAD18") (pin "1") (pinfunction "P_1") (pintype "passive"))
    )
    (net (code "70") (name "Net-(PAD19-P)") (class "Default")
      (node (ref "C8") (pin "1") (pinfunction "1_1") (pintype "passive"))
      (node (ref "PAD19") (pin "1") (pinfunction "P_1") (pintype "passive"))
    )
    (net (code "71") (name "Net-(PAD22-P)") (class "Default")
      (node (ref "C7") (pin "2") (pinfunction "2_2") (pintype "passive"))
      (node (ref "PAD22") (pin "1") (pinfunction "P_1") (pintype "passive"))
    )
    (net (code "72") (name "Net-(PAD28-P)") (class "Default")
      (node (ref "C11") (pin "2") (pinfunction "2_2") (pintype "passive"))
      (node (ref "PAD28") (pin "1") (pinfunction "P_1") (pintype "passive"))
    )
    (net (code "73") (name "Net-(PAD30-P)") (class "Default")
      (node (ref "C12") (pin "2") (pinfunction "2_2") (pintype "passive"))
      (node (ref "PAD30") (pin "1") (pinfunction "P_1") (pintype "passive"))
    )
    (net (code "74") (name "Net-(PAD33-P)") (class "Default")
      (node (ref "PAD33") (pin "1") (pinfunction "P_1") (pintype "passive"))
      (node (ref "R3") (pin "1") (pinfunction "1_1") (pintype "passive"))
    )
    (net (code "75") (name "Net-(PAD39-P)") (class "Default")
      (node (ref "PAD39") (pin "1") (pinfunction "P_1") (pintype "passive"))
      (node (ref "R3") (pin "2") (pinfunction "2_2") (pintype "passive"))
    )
    (net (code "76") (name "Net-(PAD40-P)") (class "Default")
      (node (ref "C13") (pin "2") (pinfunction "2_2") (pintype "passive"))
      (node (ref "PAD40") (pin "1") (pinfunction "P_1") (pintype "passive"))
    )
    (net (code "77") (name "Net-(TSSOP-16-GPIO0)") (class "Default")
      (node (ref "J5") (pin "1") (pinfunction "1_1") (pintype "bidirectional"))
      (node (ref "TSSOP-16") (pin "9") (pinfunction "GPIO0_9") (pintype "bidirectional"))
    )
    (net (code "78") (name "Net-(TSSOP-16-GPIO1)") (class "Default")
      (node (ref "J5") (pin "8") (pinfunction "8_8") (pintype "bidirectional"))
      (node (ref "TSSOP-16") (pin "16") (pinfunction "GPIO1_16") (pintype "bidirectional"))
    )
    (net (code "79") (name "Net-(TSSOP-16-GPIO2)") (class "Default")
      (node (ref "J6") (pin "7") (pinfunction "7_7") (pintype "bidirectional"))
      (node (ref "TSSOP-16") (pin "7") (pinfunction "GPIO2_7") (pintype "bidirectional"))
    )
    (net (code "80") (name "Net-(TSSOP-16-GPIO3)") (class "Default")
      (node (ref "J6") (pin "6") (pinfunction "6_6") (pintype "bidirectional"))
      (node (ref "TSSOP-16") (pin "6") (pinfunction "GPIO3_6") (pintype "bidirectional"))
    )
    (net (code "81") (name "Net-(TSSOP-16-GPIO4)") (class "Default")
      (node (ref "J6") (pin "8") (pinfunction "8_8") (pintype "bidirectional"))
      (node (ref "TSSOP-16") (pin "8") (pinfunction "GPIO4_8") (pintype "bidirectional"))
    )
    (net (code "82") (name "Net-(TSSOP-16-GPIO5)") (class "Default")
      (node (ref "J5") (pin "6") (pinfunction "6_6") (pintype "bidirectional"))
      (node (ref "TSSOP-16") (pin "14") (pinfunction "GPIO5_14") (pintype "bidirectional"))
    )
    (net (code "83") (name "Net-(TSSOP-16-GPIO6)") (class "Default")
      (node (ref "J6") (pin "3") (pinfunction "3_3") (pintype "bidirectional"))
      (node (ref "TSSOP-16") (pin "3") (pinfunction "GPIO6_3") (pintype "bidirectional"))
    )
    (net (code "84") (name "Net-(TSSOP-16-GPIO7)") (class "Default")
      (node (ref "J6") (pin "5") (pinfunction "5_5") (pintype "bidirectional"))
      (node (ref "TSSOP-16") (pin "5") (pinfunction "GPIO7_5") (pintype "bidirectional"))
    )
    (net (code "85") (name "Net-(TSSOP-16-RX)") (class "Default")
      (node (ref "J5") (pin "2") (pinfunction "2_2") (pintype "bidirectional"))
      (node (ref "TSSOP-16") (pin "10") (pinfunction "RX_10") (pintype "input"))
    )
    (net (code "86") (name "Net-(TSSOP-16-SCL)") (class "Default")
      (node (ref "J6") (pin "2") (pinfunction "2_2") (pintype "bidirectional"))
      (node (ref "TSSOP-16") (pin "2") (pinfunction "SCL_2") (pintype "output"))
    )
    (net (code "87") (name "Net-(TSSOP-16-SDA)") (class "Default")
      (node (ref "J6") (pin "1") (pinfunction "1_1") (pintype "bidirectional"))
      (node (ref "TSSOP-16") (pin "1") (pinfunction "SDA_1") (pintype "bidirectional"))
    )
    (net (code "88") (name "Net-(TSSOP-16-TX)") (class "Default")
      (node (ref "J5") (pin "3") (pinfunction "3_3") (pintype "bidirectional"))
      (node (ref "TSSOP-16") (pin "11") (pinfunction "TX_11") (pintype "output"))
    )
    (net (code "89") (name "Net-(TSSOP-16-VDD)") (class "Default")
      (node (ref "J5") (pin "4") (pinfunction "4_4") (pintype "bidirectional"))
      (node (ref "TSSOP-16") (pin "12") (pinfunction "VDD_12") (pintype "power_in"))
    )
    (net (code "90") (name "Net-(TSSOP-16-VREFP)") (class "Default")
      (node (ref "J5") (pin "7") (pinfunction "7_7") (pintype "bidirectional"))
      (node (ref "TSSOP-16") (pin "15") (pinfunction "VREFP_15") (pintype "input"))
    )
    (net (code "91") (name "Net-(TSSOP-16-VSS)") (class "Default")
      (node (ref "J5") (pin "5") (pinfunction "5_5") (pintype "bidirectional"))
      (node (ref "TSSOP-16") (pin "13") (pinfunction "VSS_13") (pintype "passive"))
    )
    (net (code "92") (name "Net-(TSSOP-16-~{RESET})") (class "Default")
      (node (ref "J6") (pin "4") (pinfunction "4_4") (pintype "bidirectional"))
      (node (ref "TSSOP-16") (pin "4") (pinfunction "~{RESET}_4") (pintype "input"))
    )
    (net (code "93") (name "Net-(TSSOP-20-A1)") (class "Default")
      (node (ref "J1") (pin "2") (pinfunction "2_2") (pintype "bidirectional"))
      (node (ref "TSSOP-20") (pin "2") (pinfunction "A1_2") (pintype "bidirectional"))
    )
    (net (code "94") (name "Net-(TSSOP-20-A2)") (class "Default")
      (node (ref "J1") (pin "3") (pinfunction "3_3") (pintype "bidirectional"))
      (node (ref "TSSOP-20") (pin "3") (pinfunction "A2_3") (pintype "bidirectional"))
    )
    (net (code "95") (name "Net-(TSSOP-20-A3)") (class "Default")
      (node (ref "J1") (pin "4") (pinfunction "4_4") (pintype "bidirectional"))
      (node (ref "TSSOP-20") (pin "4") (pinfunction "A3_4") (pintype "bidirectional"))
    )
    (net (code "96") (name "Net-(TSSOP-20-A4)") (class "Default")
      (node (ref "J1") (pin "5") (pinfunction "5_5") (pintype "bidirectional"))
      (node (ref "TSSOP-20") (pin "5") (pinfunction "A4_5") (pintype "bidirectional"))
    )
    (net (code "97") (name "Net-(TSSOP-20-A5)") (class "Default")
      (node (ref "J1") (pin "6") (pinfunction "6_6") (pintype "bidirectional"))
      (node (ref "TSSOP-20") (pin "6") (pinfunction "A5_6") (pintype "bidirectional"))
    )
    (net (code "98") (name "Net-(TSSOP-20-A6)") (class "Default")
      (node (ref "J1") (pin "7") (pinfunction "7_7") (pintype "bidirectional"))
      (node (ref "TSSOP-20") (pin "7") (pinfunction "A6_7") (pintype "bidirectional"))
    )
    (net (code "99") (name "Net-(TSSOP-20-A7)") (class "Default")
      (node (ref "J1") (pin "8") (pinfunction "8_8") (pintype "bidirectional"))
      (node (ref "TSSOP-20") (pin "8") (pinfunction "A7_8") (pintype "bidirectional"))
    )
    (net (code "100") (name "Net-(TSSOP-20-A8)") (class "Default")
      (node (ref "J1") (pin "9") (pinfunction "9_9") (pintype "bidirectional"))
      (node (ref "TSSOP-20") (pin "9") (pinfunction "A8_9") (pintype "bidirectional"))
    )
    (net (code "101") (name "Net-(TSSOP-20-B1)") (class "Default")
      (node (ref "J2") (pin "8") (pinfunction "8_8") (pintype "bidirectional"))
      (node (ref "TSSOP-20") (pin "18") (pinfunction "B1_18") (pintype "bidirectional"))
    )
    (net (code "102") (name "Net-(TSSOP-20-B2)") (class "Default")
      (node (ref "J2") (pin "7") (pinfunction "7_7") (pintype "bidirectional"))
      (node (ref "TSSOP-20") (pin "17") (pinfunction "B2_17") (pintype "bidirectional"))
    )
    (net (code "103") (name "Net-(TSSOP-20-B3)") (class "Default")
      (node (ref "J2") (pin "6") (pinfunction "6_6") (pintype "bidirectional"))
      (node (ref "TSSOP-20") (pin "16") (pinfunction "B3_16") (pintype "bidirectional"))
    )
    (net (code "104") (name "Net-(TSSOP-20-B4)") (class "Default")
      (node (ref "J2") (pin "5") (pinfunction "5_5") (pintype "bidirectional"))
      (node (ref "TSSOP-20") (pin "15") (pinfunction "B4_15") (pintype "bidirectional"))
    )
    (net (code "105") (name "Net-(TSSOP-20-B5)") (class "Default")
      (node (ref "J2") (pin "4") (pinfunction "4_4") (pintype "bidirectional"))
      (node (ref "TSSOP-20") (pin "14") (pinfunction "B5_14") (pintype "bidirectional"))
    )
    (net (code "106") (name "Net-(TSSOP-20-B6)") (class "Default")
      (node (ref "J2") (pin "3") (pinfunction "3_3") (pintype "bidirectional"))
      (node (ref "TSSOP-20") (pin "13") (pinfunction "B6_13") (pintype "bidirectional"))
    )
    (net (code "107") (name "Net-(TSSOP-20-B7)") (class "Default")
      (node (ref "J2") (pin "2") (pinfunction "2_2") (pintype "bidirectional"))
      (node (ref "TSSOP-20") (pin "12") (pinfunction "B7_12") (pintype "bidirectional"))
    )
    (net (code "108") (name "Net-(TSSOP-20-B8)") (class "Default")
      (node (ref "J2") (pin "1") (pinfunction "1_1") (pintype "bidirectional"))
      (node (ref "TSSOP-20") (pin "11") (pinfunction "B8_11") (pintype "bidirectional"))
    )
    (net (code "109") (name "Net-(TSSOP-20-DIR)") (class "Default")
      (node (ref "J1") (pin "1") (pinfunction "1_1") (pintype "bidirectional"))
      (node (ref "TSSOP-20") (pin "1") (pinfunction "DIR_1") (pintype "input"))
    )
    (net (code "110") (name "Net-(TSSOP-20-GND)") (class "Default")
      (node (ref "J1") (pin "10") (pinfunction "10_10") (pintype "bidirectional"))
      (node (ref "TSSOP-20") (pin "10") (pinfunction "GND_10") (pintype "power_in"))
    )
    (net (code "111") (name "Net-(TSSOP-20-VCC)") (class "Default")
      (node (ref "J2") (pin "10") (pinfunction "10_10") (pintype "bidirectional"))
      (node (ref "TSSOP-20") (pin "20") (pinfunction "VCC_20") (pintype "power_in"))
    )
    (net (code "112") (name "Net-(TSSOP-20-~{OE})") (class "Default")
      (node (ref "J2") (pin "9") (pinfunction "9_9") (pintype "bidirectional"))
      (node (ref "TSSOP-20") (pin "19") (pinfunction "~{OE}_19") (pintype "input"))
    )
    (net (code "113") (name "Net-(U3-FB)") (class "Default")
      (node (ref "C10") (pin "1") (pinfunction "1_1") (pintype "passive"))
      (node (ref "R1") (pin "1") (pinfunction "1_1") (pintype "passive"))
      (node (ref "R2") (pin "1") (pinfunction "1_1") (pintype "passive"))
      (node (ref "R2") (pin "2") (pinfunction "2_2") (pintype "passive"))
      (node (ref "U3") (pin "4") (pinfunction "FB_4") (pintype "input"))
      (node (ref "U3") (pin "5") (pinfunction "OUT_5") (pintype "output"))
      (node (ref "U4") (pin "1") (pinfunction "CH1+_1") (pintype "input"))
    )
    (net (code "114") (name "Net-(U3-IN-)") (class "Default")
      (node (ref "C10") (pin "2") (pinfunction "2_2") (pintype "passive"))
      (node (ref "R1") (pin "2") (pinfunction "2_2") (pintype "passive"))
      (node (ref "U3") (pin "2") (pinfunction "IN-_2") (pintype "input"))
    )
    (net (code "115") (name "unconnected-(CLGA-7-PAD2LID-Pad7)") (class "Default")
      (node (ref "CLGA-7") (pin "7") (pinfunction "PAD2LID_7") (pintype "bidirectional"))
    )
    (net (code "116") (name "unconnected-(U3-NC-Pad7)") (class "Default")
      (node (ref "U3") (pin "7") (pinfunction "NC_7") (pintype "passive"))
    )
    (net (code "117") (name "unconnected-(U3-NC_2-Pad6)") (class "Default")
      (node (ref "U3") (pin "6") (pinfunction "NC_2_6") (pintype "passive"))
    )
  )
)
